# 3MIC_backplaneREVA.net
KiCad netlist of a schematic drawn in EAGLE
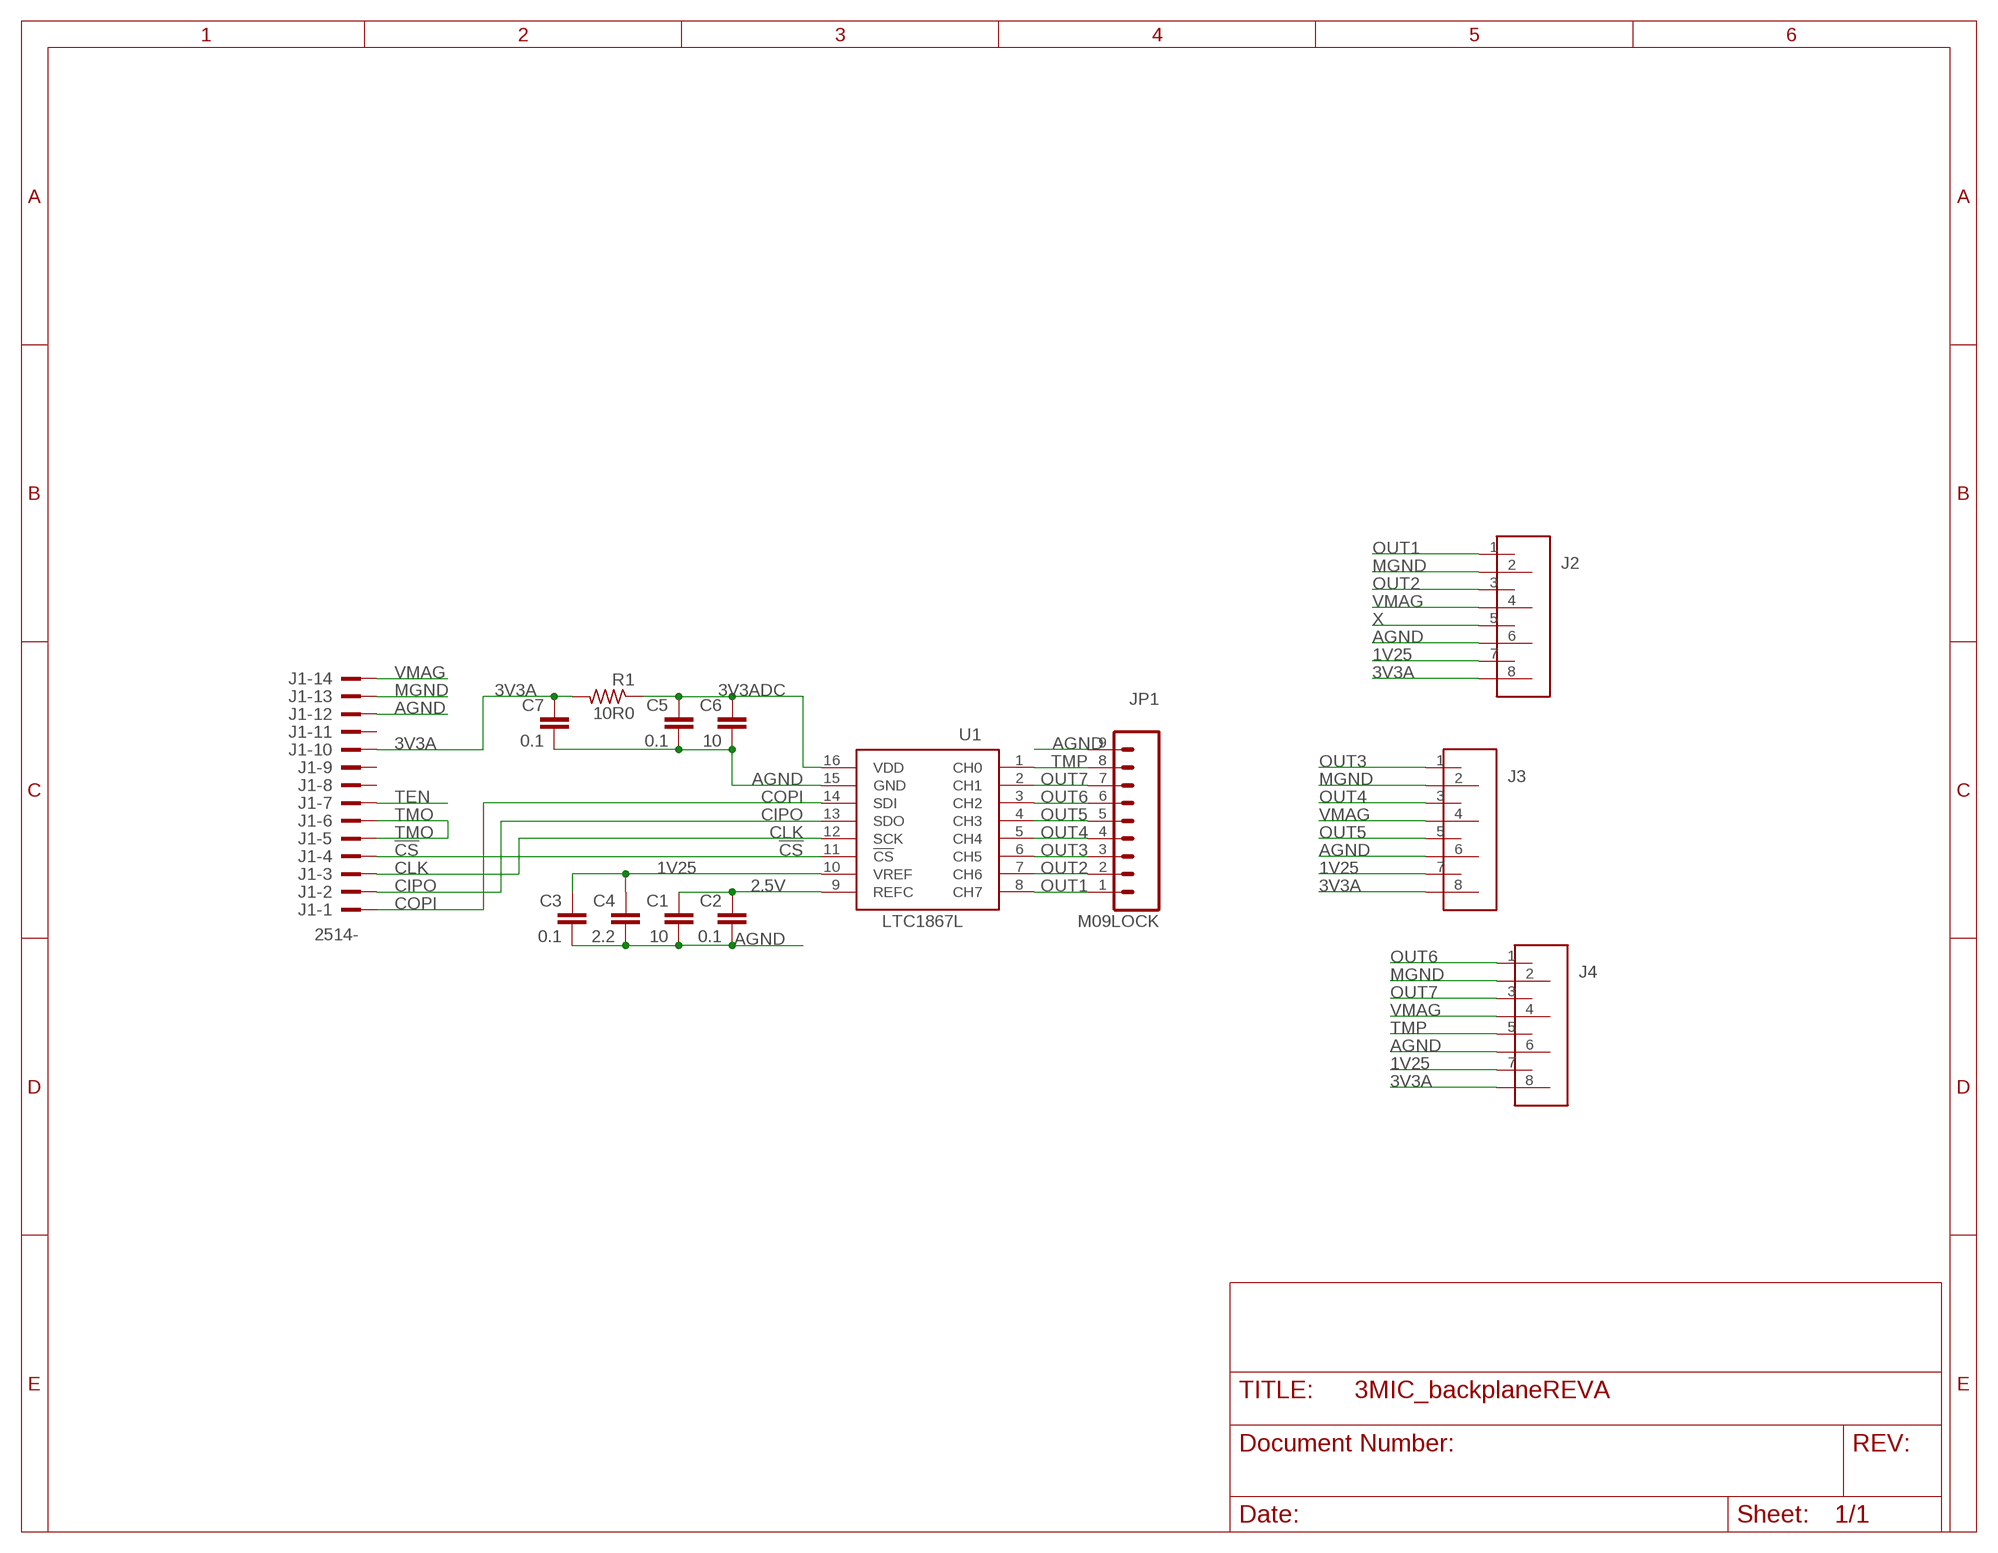
[diagram p0: schematic, sheet 1]

(export (version "E")
  (design (tool "Eeschema 10.0.6"))
  (components
    (comp (ref "C1")
      (value "10")
      (footprint "eagle-import:0805S")
      (libsource (lib "eagle-import") (part "CAPS0805S"))
    )
    (comp (ref "C2")
      (value "0.1")
      (footprint "eagle-import:0603S")
      (libsource (lib "eagle-import") (part "CAPS0603S"))
    )
    (comp (ref "C3")
      (value "0.1")
      (footprint "eagle-import:0603S")
      (libsource (lib "eagle-import") (part "CAPS0603S"))
    )
    (comp (ref "C4")
      (value "2.2")
      (footprint "eagle-import:0805S")
      (libsource (lib "eagle-import") (part "CAPS0805S"))
    )
    (comp (ref "C5")
      (value "0.1")
      (footprint "eagle-import:0603S")
      (libsource (lib "eagle-import") (part "CAPS0603S"))
    )
    (comp (ref "C6")
      (value "10")
      (footprint "eagle-import:0805S")
      (libsource (lib "eagle-import") (part "CAPS0805S"))
    )
    (comp (ref "C7")
      (value "0.1")
      (footprint "eagle-import:0603S")
      (libsource (lib "eagle-import") (part "CAPS0603S"))
    )
    (comp (ref "J1")
      (value "2514-")
      (footprint "eagle-import:PAK100_2500-14")
      (libsource (lib "eagle-import") (part "2514-"))
    )
    (comp (ref "J2")
      (value "CON84X2SHROUDED")
      (footprint "eagle-import:4X2SHROUDED")
      (libsource (lib "eagle-import") (part "CON84X2SHROUDED"))
    )
    (comp (ref "J3")
      (value "CON84X2SHROUDED")
      (footprint "eagle-import:4X2SHROUDED")
      (libsource (lib "eagle-import") (part "CON84X2SHROUDED"))
    )
    (comp (ref "J4")
      (value "CON84X2SHROUDED")
      (footprint "eagle-import:4X2SHROUDED")
      (libsource (lib "eagle-import") (part "CON84X2SHROUDED"))
    )
    (comp (ref "JP1")
      (value "M09LOCK")
      (footprint "eagle-import:1X09_LOCK")
      (libsource (lib "eagle-import") (part "M09LOCK"))
    )
    (comp (ref "R1")
      (value "10R0")
      (footprint "eagle-import:0805S")
      (libsource (lib "eagle-import") (part "RESISTOR_SM0805S"))
    )
    (comp (ref "U1")
      (value "LTC1867L")
      (footprint "eagle-import:SSOP16")
      (libsource (lib "eagle-import") (part "LTC1867"))
    )
  )
  (nets
    (net (code "1") (name "/1V25") (class "Default")
      (node (ref "C3") (pin "1") (pinfunction "1_1") (pintype "passive"))
      (node (ref "C4") (pin "1") (pinfunction "1_1") (pintype "passive"))
      (node (ref "J2") (pin "7") (pinfunction "7_7") (pintype "bidirectional"))
      (node (ref "J3") (pin "7") (pinfunction "7_7") (pintype "bidirectional"))
      (node (ref "J4") (pin "7") (pinfunction "7_7") (pintype "bidirectional"))
      (node (ref "U1") (pin "10") (pinfunction "VREF_10") (pintype "bidirectional"))
    )
    (net (code "2") (name "/2.5V") (class "Default")
      (node (ref "C1") (pin "1") (pinfunction "1_1") (pintype "passive"))
      (node (ref "C2") (pin "1") (pinfunction "1_1") (pintype "passive"))
      (node (ref "U1") (pin "9") (pinfunction "REFC_9") (pintype "bidirectional"))
    )
    (net (code "3") (name "/3V3A") (class "Default")
      (node (ref "C7") (pin "1") (pinfunction "1_1") (pintype "passive"))
      (node (ref "J1") (pin "10") (pinfunction "KL_10") (pintype "passive"))
      (node (ref "J2") (pin "8") (pinfunction "8_8") (pintype "bidirectional"))
      (node (ref "J3") (pin "8") (pinfunction "8_8") (pintype "bidirectional"))
      (node (ref "J4") (pin "8") (pinfunction "8_8") (pintype "bidirectional"))
      (node (ref "R1") (pin "2") (pinfunction "2_2") (pintype "passive"))
    )
    (net (code "4") (name "/3V3ADC") (class "Default")
      (node (ref "C5") (pin "1") (pinfunction "1_1") (pintype "passive"))
      (node (ref "C6") (pin "1") (pinfunction "1_1") (pintype "passive"))
      (node (ref "R1") (pin "1") (pinfunction "1_1") (pintype "passive"))
      (node (ref "U1") (pin "16") (pinfunction "VDD_16") (pintype "bidirectional"))
    )
    (net (code "5") (name "/AGND") (class "Default")
      (node (ref "C1") (pin "2") (pinfunction "2_2") (pintype "passive"))
      (node (ref "C2") (pin "2") (pinfunction "2_2") (pintype "passive"))
      (node (ref "C3") (pin "2") (pinfunction "2_2") (pintype "passive"))
      (node (ref "C4") (pin "2") (pinfunction "2_2") (pintype "passive"))
      (node (ref "C5") (pin "2") (pinfunction "2_2") (pintype "passive"))
      (node (ref "C6") (pin "2") (pinfunction "2_2") (pintype "passive"))
      (node (ref "C7") (pin "2") (pinfunction "2_2") (pintype "passive"))
      (node (ref "J1") (pin "12") (pinfunction "KL_12") (pintype "passive"))
      (node (ref "J2") (pin "6") (pinfunction "6_6") (pintype "bidirectional"))
      (node (ref "J3") (pin "6") (pinfunction "6_6") (pintype "bidirectional"))
      (node (ref "J4") (pin "6") (pinfunction "6_6") (pintype "bidirectional"))
      (node (ref "JP1") (pin "9") (pinfunction "9_9") (pintype "passive"))
      (node (ref "U1") (pin "15") (pinfunction "GND_15") (pintype "bidirectional"))
    )
    (net (code "6") (name "/CIPO") (class "Default")
      (node (ref "J1") (pin "2") (pinfunction "KL_2") (pintype "passive"))
      (node (ref "U1") (pin "13") (pinfunction "SDO_13") (pintype "bidirectional"))
    )
    (net (code "7") (name "/CLK") (class "Default")
      (node (ref "J1") (pin "3") (pinfunction "KL_3") (pintype "passive"))
      (node (ref "U1") (pin "12") (pinfunction "SCK_12") (pintype "bidirectional"))
    )
    (net (code "8") (name "/COPI") (class "Default")
      (node (ref "J1") (pin "1") (pinfunction "KL_1") (pintype "passive"))
      (node (ref "U1") (pin "14") (pinfunction "SDI_14") (pintype "bidirectional"))
    )
    (net (code "9") (name "/MGND") (class "Default")
      (node (ref "J1") (pin "13") (pinfunction "KL_13") (pintype "passive"))
      (node (ref "J2") (pin "2") (pinfunction "2_2") (pintype "bidirectional"))
      (node (ref "J3") (pin "2") (pinfunction "2_2") (pintype "bidirectional"))
      (node (ref "J4") (pin "2") (pinfunction "2_2") (pintype "bidirectional"))
    )
    (net (code "10") (name "/OUT1") (class "Default")
      (node (ref "J2") (pin "1") (pinfunction "1_1") (pintype "bidirectional"))
      (node (ref "JP1") (pin "1") (pinfunction "1_1") (pintype "passive"))
      (node (ref "U1") (pin "8") (pinfunction "CH7_8") (pintype "bidirectional"))
    )
    (net (code "11") (name "/OUT2") (class "Default")
      (node (ref "J2") (pin "3") (pinfunction "3_3") (pintype "bidirectional"))
      (node (ref "JP1") (pin "2") (pinfunction "2_2") (pintype "passive"))
      (node (ref "U1") (pin "7") (pinfunction "CH6_7") (pintype "bidirectional"))
    )
    (net (code "12") (name "/OUT3") (class "Default")
      (node (ref "J3") (pin "1") (pinfunction "1_1") (pintype "bidirectional"))
      (node (ref "JP1") (pin "3") (pinfunction "3_3") (pintype "passive"))
      (node (ref "U1") (pin "6") (pinfunction "CH5_6") (pintype "bidirectional"))
    )
    (net (code "13") (name "/OUT4") (class "Default")
      (node (ref "J3") (pin "3") (pinfunction "3_3") (pintype "bidirectional"))
      (node (ref "JP1") (pin "4") (pinfunction "4_4") (pintype "passive"))
      (node (ref "U1") (pin "5") (pinfunction "CH4_5") (pintype "bidirectional"))
    )
    (net (code "14") (name "/OUT5") (class "Default")
      (node (ref "J3") (pin "5") (pinfunction "5_5") (pintype "bidirectional"))
      (node (ref "JP1") (pin "5") (pinfunction "5_5") (pintype "passive"))
      (node (ref "U1") (pin "4") (pinfunction "CH3_4") (pintype "bidirectional"))
    )
    (net (code "15") (name "/OUT6") (class "Default")
      (node (ref "J4") (pin "1") (pinfunction "1_1") (pintype "bidirectional"))
      (node (ref "JP1") (pin "6") (pinfunction "6_6") (pintype "passive"))
      (node (ref "U1") (pin "3") (pinfunction "CH2_3") (pintype "bidirectional"))
    )
    (net (code "16") (name "/OUT7") (class "Default")
      (node (ref "J4") (pin "3") (pinfunction "3_3") (pintype "bidirectional"))
      (node (ref "JP1") (pin "7") (pinfunction "7_7") (pintype "passive"))
      (node (ref "U1") (pin "2") (pinfunction "CH1_2") (pintype "bidirectional"))
    )
    (net (code "17") (name "/TEN") (class "Default")
      (node (ref "J1") (pin "7") (pinfunction "KL_7") (pintype "passive"))
    )
    (net (code "18") (name "/TMO") (class "Default")
      (node (ref "J1") (pin "5") (pinfunction "KL_5") (pintype "passive"))
      (node (ref "J1") (pin "6") (pinfunction "KL_6") (pintype "passive"))
    )
    (net (code "19") (name "/TMP") (class "Default")
      (node (ref "J4") (pin "5") (pinfunction "5_5") (pintype "bidirectional"))
      (node (ref "JP1") (pin "8") (pinfunction "8_8") (pintype "passive"))
      (node (ref "U1") (pin "1") (pinfunction "CH0_1") (pintype "bidirectional"))
    )
    (net (code "20") (name "/VMAG") (class "Default")
      (node (ref "J1") (pin "14") (pinfunction "KL_14") (pintype "passive"))
      (node (ref "J2") (pin "4") (pinfunction "4_4") (pintype "bidirectional"))
      (node (ref "J3") (pin "4") (pinfunction "4_4") (pintype "bidirectional"))
      (node (ref "J4") (pin "4") (pinfunction "4_4") (pintype "bidirectional"))
    )
    (net (code "21") (name "/X") (class "Default")
      (node (ref "J2") (pin "5") (pinfunction "5_5") (pintype "bidirectional"))
    )
    (net (code "22") (name "/~{CS}") (class "Default")
      (node (ref "J1") (pin "4") (pinfunction "KL_4") (pintype "passive"))
      (node (ref "U1") (pin "11") (pinfunction "~{CS}_11") (pintype "bidirectional"))
    )
    (net (code "23") (name "unconnected-(J1C-KL-Pad11)") (class "Default")
      (node (ref "J1") (pin "11") (pinfunction "KL_11") (pintype "passive"))
    )
    (net (code "24") (name "unconnected-(J1M-KL-Pad8)") (class "Default")
      (node (ref "J1") (pin "8") (pinfunction "KL_8") (pintype "passive"))
    )
    (net (code "25") (name "unconnected-(J1N-KL-Pad9)") (class "Default")
      (node (ref "J1") (pin "9") (pinfunction "KL_9") (pintype "passive"))
    )
  )
)
